# AccessControlBoard.net
KiCad netlist of a schematic drawn in EAGLE
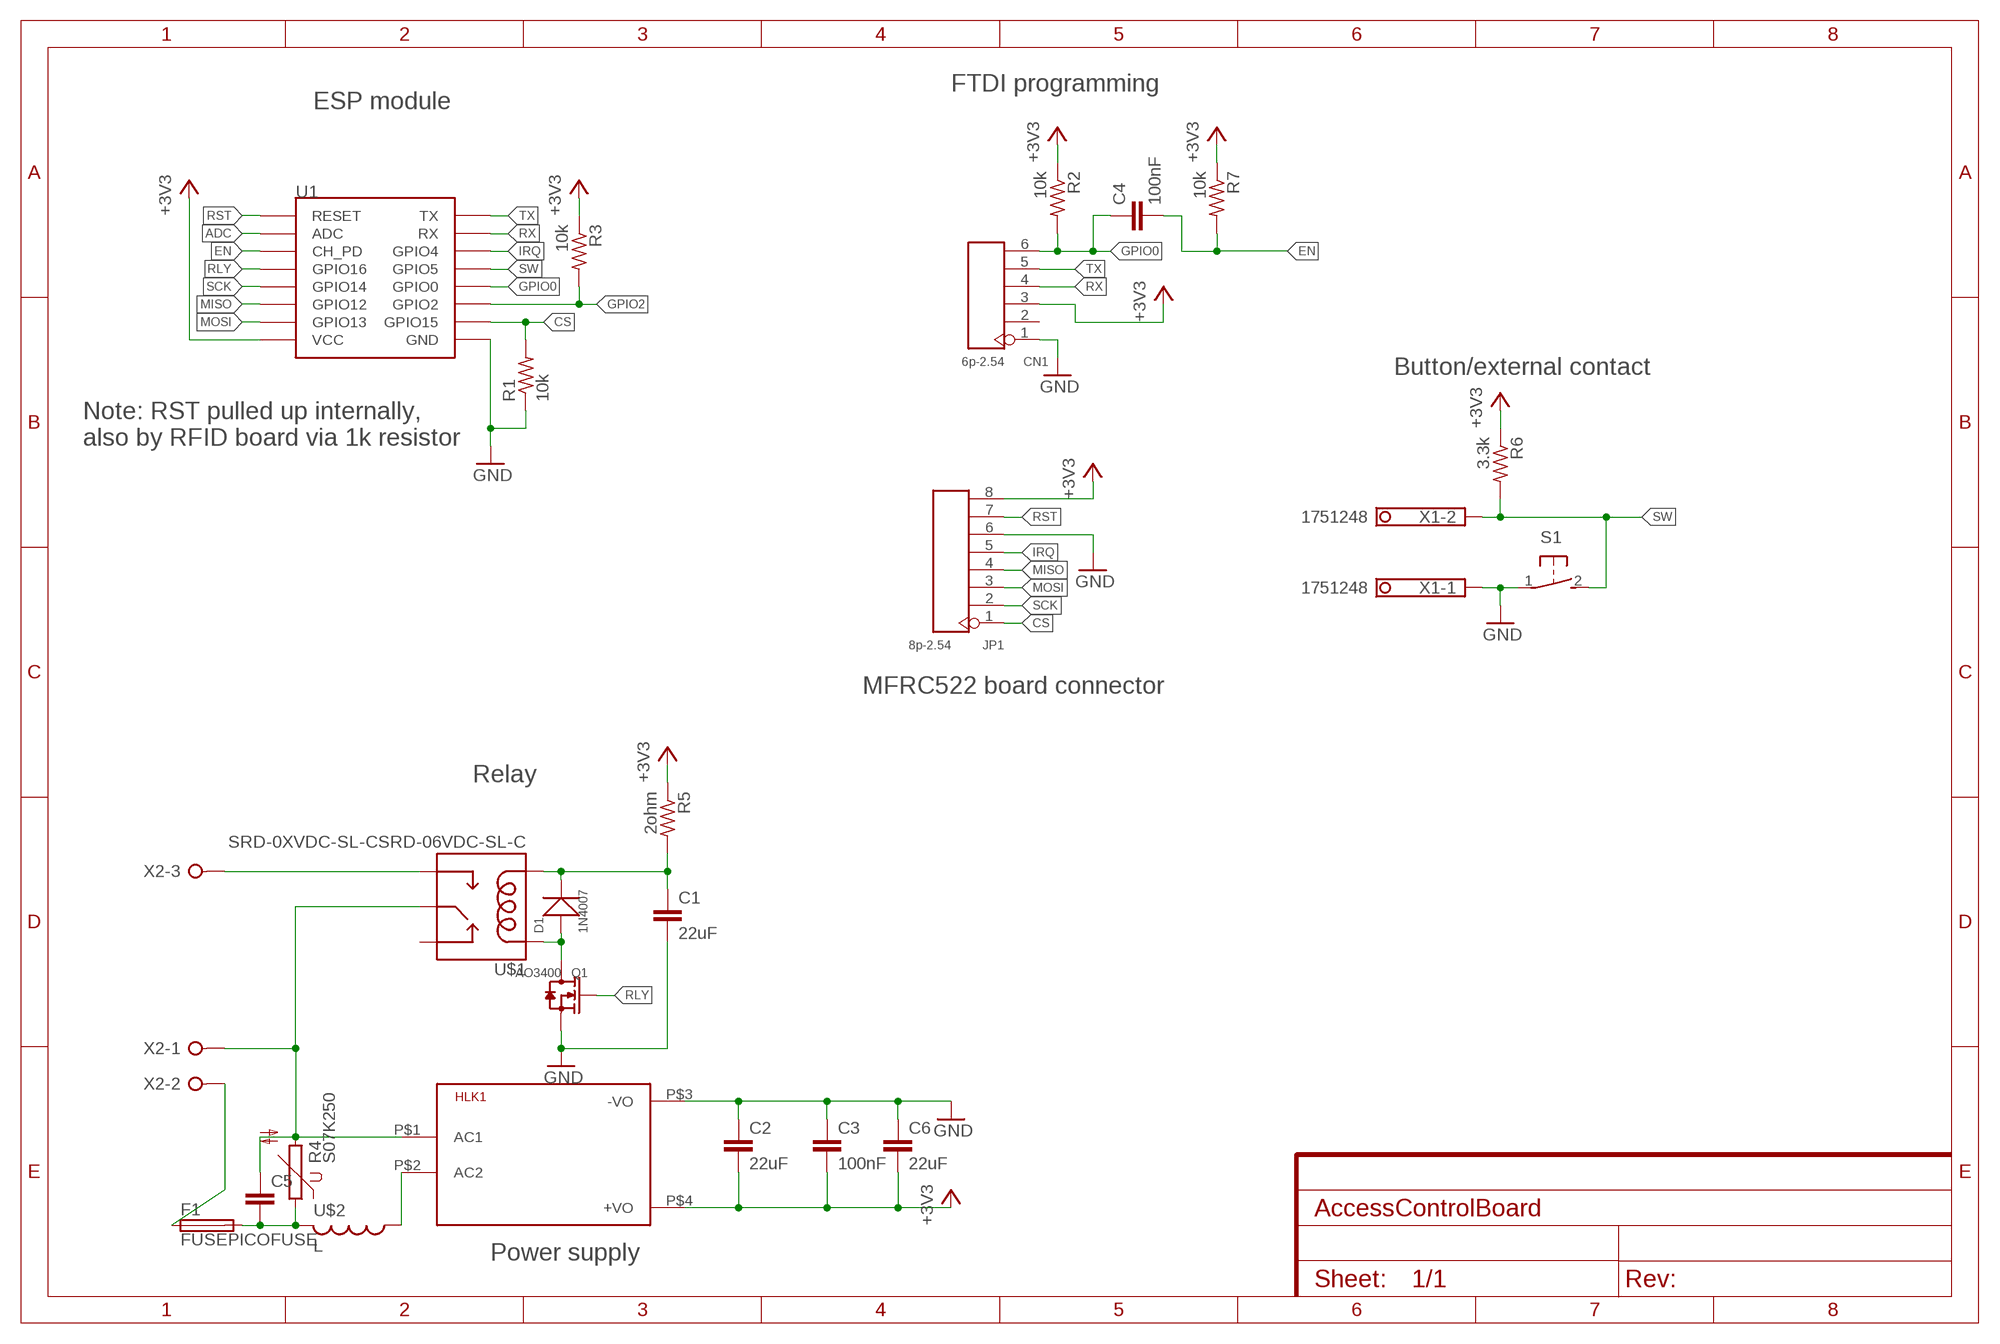
[diagram p0: schematic, sheet 1]

(export (version "E")
  (design (tool "Eeschema 10.0.6"))
  (components
    (comp (ref "C1")
      (value "22uF")
      (footprint "eagle-import:C0805K")
      (libsource (lib "eagle-import") (part "C-EUC0805K"))
    )
    (comp (ref "C2")
      (value "22uF")
      (footprint "eagle-import:C0805K")
      (libsource (lib "eagle-import") (part "C-EUC0805K"))
    )
    (comp (ref "C3")
      (value "100nF")
      (footprint "eagle-import:C0603K")
      (libsource (lib "eagle-import") (part "C-EUC0603K"))
    )
    (comp (ref "C4")
      (value "100nF")
      (footprint "eagle-import:C0603K")
      (libsource (lib "eagle-import") (part "C-EUC0603K"))
    )
    (comp (ref "C5")
      (value "C-EU102-064X133")
      (footprint "eagle-import:C102-064X133")
      (libsource (lib "eagle-import") (part "C-EU102-064X133"))
    )
    (comp (ref "C6")
      (value "22uF")
      (footprint "eagle-import:C0805K")
      (libsource (lib "eagle-import") (part "C-EUC0805K"))
    )
    (comp (ref "CN1")
      (value "6p-2.54")
      (footprint "eagle-import:H6-2.54")
      (fields (field (name "MPN") "F185-1106A1BSYC1"))
      (libsource (lib "eagle-import") (part "DIP-BLACK-FEMALE-HEADER-VERT(6P-2.54)"))
    )
    (comp (ref "D1")
      (value "1N4007")
      (footprint "eagle-import:DO-214AC")
      (libsource (lib "eagle-import") (part "DIODE-GEN-PURPOSE-1KV-1A(DO-214AC)"))
    )
    (comp (ref "F1")
      (value "FUSEPICOFUSE")
      (footprint "eagle-import:PICOFUSE")
      (libsource (lib "eagle-import") (part "FUSEPICOFUSE"))
    )
    (comp (ref "HLK1")
      (value "HLK-PM013W")
      (footprint "eagle-import:HLK-PM01")
      (libsource (lib "eagle-import") (part "HLK-PM013W"))
    )
    (comp (ref "JP1")
      (value "8p-2.54")
      (footprint "eagle-import:H8-2.54")
      (fields (field (name "MPN") "P125-1108A1BS116A1"))
      (libsource (lib "eagle-import") (part "DIP-BLACK-MALE-HEADER-VERT(8P-2.54)"))
    )
    (comp (ref "Q1")
      (value "AO3400")
      (footprint "eagle-import:SOT-23")
      (fields (field (name "MPN") "2N7002,215"))
      (libsource (lib "eagle-import") (part "SMD-MOSFET-N-CH-60V-300MA-LOGIC-LEVEL-FET-2N7002(SOT-23)"))
    )
    (comp (ref "R1")
      (value "10k")
      (footprint "eagle-import:R0603")
      (libsource (lib "eagle-import") (part "R-US_R0603"))
    )
    (comp (ref "R2")
      (value "10k")
      (footprint "eagle-import:R0603")
      (libsource (lib "eagle-import") (part "R-US_R0603"))
    )
    (comp (ref "R3")
      (value "10k")
      (footprint "eagle-import:R0603")
      (libsource (lib "eagle-import") (part "R-US_R0603"))
    )
    (comp (ref "R4")
      (value "S07K250")
      (footprint "eagle-import:S07K250")
      (libsource (lib "eagle-import") (part "S07K250"))
    )
    (comp (ref "R5")
      (value "2ohm")
      (footprint "eagle-import:R0603")
      (libsource (lib "eagle-import") (part "R-US_R0603"))
    )
    (comp (ref "R6")
      (value "3.3k")
      (footprint "eagle-import:R0603")
      (libsource (lib "eagle-import") (part "R-US_R0603"))
    )
    (comp (ref "R7")
      (value "10k")
      (footprint "eagle-import:R0603")
      (libsource (lib "eagle-import") (part "R-US_R0603"))
    )
    (comp (ref "S1")
      (value "31-XX")
      (footprint "eagle-import:B3F-31XX")
      (fields (field (name "MPN") "B3F-3100"))
      (libsource (lib "eagle-import") (part "31-XX"))
    )
    (comp (ref "U$1")
      (value "SRD-0XVDC-SL-CSRD-06VDC-SL-C")
      (footprint "eagle-import:SRD-0XVDC-SL-C")
      (libsource (lib "eagle-import") (part "SRD-0XVDC-SL-CSRD-06VDC-SL-C"))
    )
    (comp (ref "U$2") (value "L") (footprint "eagle-import:6000") (libsource (lib "eagle-import") (part "L")))
    (comp (ref "U1")
      (value "ESP12SMD")
      (footprint "eagle-import:ESP12-SMD")
      (libsource (lib "eagle-import") (part "ESP12SMD"))
    )
    (comp (ref "X1")
      (value "1751248")
      (footprint "eagle-import:1751248")
      (libsource (lib "eagle-import") (part "1751248"))
    )
    (comp (ref "X2")
      (value "W237-3E")
      (footprint "eagle-import:W237-3E")
      (libsource (lib "eagle-import") (part "W237-3E"))
    )
  )
  (nets
    (net (code "1") (name "+3V3") (class "Default")
      (node (ref "C2") (pin "2") (pinfunction "2_2") (pintype "passive"))
      (node (ref "C3") (pin "2") (pinfunction "2_2") (pintype "passive"))
      (node (ref "C6") (pin "2") (pinfunction "2_2") (pintype "passive"))
      (node (ref "CN1") (pin "3") (pinfunction "3_3") (pintype "bidirectional"))
      (node (ref "HLK1") (pin "P$4") (pinfunction "+VO_P$4") (pintype "bidirectional"))
      (node (ref "JP1") (pin "8") (pinfunction "8_8") (pintype "bidirectional"))
      (node (ref "R2") (pin "1") (pinfunction "1_1") (pintype "passive"))
      (node (ref "R3") (pin "1") (pinfunction "1_1") (pintype "passive"))
      (node (ref "R5") (pin "1") (pinfunction "1_1") (pintype "passive"))
      (node (ref "R6") (pin "1") (pinfunction "1_1") (pintype "passive"))
      (node (ref "R7") (pin "1") (pinfunction "1_1") (pintype "passive"))
      (node (ref "U1") (pin "VCC") (pinfunction "VCC_VCC") (pintype "bidirectional"))
    )
    (net (code "2") (name "ADC") (class "Default")
      (node (ref "U1") (pin "ADC") (pinfunction "ADC_ADC") (pintype "bidirectional"))
    )
    (net (code "3") (name "CS") (class "Default")
      (node (ref "JP1") (pin "1") (pinfunction "1_1") (pintype "bidirectional"))
      (node (ref "R1") (pin "2") (pinfunction "2_2") (pintype "passive"))
      (node (ref "U1") (pin "GPIO15") (pinfunction "GPIO15_GPIO15") (pintype "bidirectional"))
    )
    (net (code "4") (name "EN") (class "Default")
      (node (ref "C4") (pin "2") (pinfunction "2_2") (pintype "passive"))
      (node (ref "R7") (pin "2") (pinfunction "2_2") (pintype "passive"))
      (node (ref "U1") (pin "CH_PD") (pinfunction "CH_PD_CH_PD") (pintype "bidirectional"))
    )
    (net (code "5") (name "GND") (class "Default")
      (node (ref "C1") (pin "2") (pinfunction "2_2") (pintype "passive"))
      (node (ref "C2") (pin "1") (pinfunction "1_1") (pintype "passive"))
      (node (ref "C3") (pin "1") (pinfunction "1_1") (pintype "passive"))
      (node (ref "C6") (pin "1") (pinfunction "1_1") (pintype "passive"))
      (node (ref "CN1") (pin "1") (pinfunction "1_1") (pintype "bidirectional"))
      (node (ref "HLK1") (pin "P$3") (pinfunction "-VO_P$3") (pintype "bidirectional"))
      (node (ref "JP1") (pin "6") (pinfunction "6_6") (pintype "bidirectional"))
      (node (ref "Q1") (pin "2") (pinfunction "S_2") (pintype "passive"))
      (node (ref "R1") (pin "1") (pinfunction "1_1") (pintype "passive"))
      (node (ref "S1") (pin "1") (pinfunction "P_1") (pintype "passive"))
      (node (ref "U1") (pin "GND") (pinfunction "GND_GND") (pintype "bidirectional"))
      (node (ref "X1") (pin "1") (pinfunction "K_1") (pintype "passive"))
    )
    (net (code "6") (name "GPIO0") (class "Default")
      (node (ref "C4") (pin "1") (pinfunction "1_1") (pintype "passive"))
      (node (ref "CN1") (pin "6") (pinfunction "6_6") (pintype "bidirectional"))
      (node (ref "R2") (pin "2") (pinfunction "2_2") (pintype "passive"))
      (node (ref "U1") (pin "GPIO0") (pinfunction "GPIO0_GPIO0") (pintype "bidirectional"))
    )
    (net (code "7") (name "GPIO2") (class "Default")
      (node (ref "R3") (pin "2") (pinfunction "2_2") (pintype "passive"))
      (node (ref "U1") (pin "GPIO2") (pinfunction "GPIO2_GPIO2") (pintype "bidirectional"))
    )
    (net (code "8") (name "IRQ") (class "Default")
      (node (ref "JP1") (pin "5") (pinfunction "5_5") (pintype "bidirectional"))
      (node (ref "U1") (pin "GPIO4") (pinfunction "GPIO4_GPIO4") (pintype "bidirectional"))
    )
    (net (code "9") (name "MISO") (class "Default")
      (node (ref "JP1") (pin "4") (pinfunction "4_4") (pintype "bidirectional"))
      (node (ref "U1") (pin "GPIO12") (pinfunction "GPIO12_GPIO12") (pintype "bidirectional"))
    )
    (net (code "10") (name "MOSI") (class "Default")
      (node (ref "JP1") (pin "3") (pinfunction "3_3") (pintype "bidirectional"))
      (node (ref "U1") (pin "GPIO13") (pinfunction "GPIO13_GPIO13") (pintype "bidirectional"))
    )
    (net (code "11") (name "Net-(C5-Pad2)") (class "Default")
      (node (ref "C5") (pin "2") (pinfunction "2_2") (pintype "passive"))
      (node (ref "F1") (pin "2") (pinfunction "2_2") (pintype "passive"))
      (node (ref "R4") (pin "1") (pinfunction "1_1") (pintype "passive"))
      (node (ref "U$2") (pin "2") (pinfunction "2_2") (pintype "passive"))
    )
    (net (code "12") (name "Net-(D1-+)") (class "Default")
      (node (ref "D1") (pin "1") (pinfunction "+_1") (pintype "passive"))
      (node (ref "Q1") (pin "3") (pinfunction "D_3") (pintype "passive"))
      (node (ref "U$1") (pin "COIL1") (pinfunction "COIL1_COIL1") (pintype "bidirectional"))
    )
    (net (code "13") (name "Net-(D1--)") (class "Default")
      (node (ref "C1") (pin "1") (pinfunction "1_1") (pintype "passive"))
      (node (ref "D1") (pin "2") (pinfunction "-_2") (pintype "passive"))
      (node (ref "R5") (pin "2") (pinfunction "2_2") (pintype "passive"))
      (node (ref "U$1") (pin "COIL0") (pinfunction "COIL0_COIL0") (pintype "bidirectional"))
    )
    (net (code "14") (name "Net-(HLK1-AC1)") (class "Default")
      (node (ref "C5") (pin "1") (pinfunction "1_1") (pintype "passive"))
      (node (ref "HLK1") (pin "P$1") (pinfunction "AC1_P$1") (pintype "bidirectional"))
      (node (ref "R4") (pin "2") (pinfunction "2_2") (pintype "passive"))
      (node (ref "U$1") (pin "SWCOMMON") (pinfunction "SWCOMMON_SWCOMMON") (pintype "bidirectional"))
      (node (ref "X2") (pin "1") (pinfunction "KL_1") (pintype "passive"))
    )
    (net (code "15") (name "Net-(HLK1-AC2)") (class "Default")
      (node (ref "HLK1") (pin "P$2") (pinfunction "AC2_P$2") (pintype "bidirectional"))
      (node (ref "U$2") (pin "1") (pinfunction "1_1") (pintype "passive"))
    )
    (net (code "16") (name "Net-(X2B-KL)") (class "Default")
      (node (ref "F1") (pin "1") (pinfunction "1_1") (pintype "passive"))
      (node (ref "X2") (pin "2") (pinfunction "KL_2") (pintype "passive"))
    )
    (net (code "17") (name "Net-(X2C-KL)") (class "Default")
      (node (ref "U$1") (pin "SWOPEN") (pinfunction "SWOPEN_SWOPEN") (pintype "bidirectional"))
      (node (ref "X2") (pin "3") (pinfunction "KL_3") (pintype "passive"))
    )
    (net (code "18") (name "RLY") (class "Default")
      (node (ref "Q1") (pin "1") (pinfunction "G_1") (pintype "passive"))
      (node (ref "U1") (pin "GPIO16") (pinfunction "GPIO16_GPIO16") (pintype "bidirectional"))
    )
    (net (code "19") (name "RST") (class "Default")
      (node (ref "JP1") (pin "7") (pinfunction "7_7") (pintype "bidirectional"))
      (node (ref "U1") (pin "RESET") (pinfunction "RESET_RESET") (pintype "bidirectional"))
    )
    (net (code "20") (name "RX") (class "Default")
      (node (ref "CN1") (pin "4") (pinfunction "4_4") (pintype "bidirectional"))
      (node (ref "U1") (pin "RXD0") (pinfunction "RX_RXD0") (pintype "bidirectional"))
    )
    (net (code "21") (name "SCK") (class "Default")
      (node (ref "JP1") (pin "2") (pinfunction "2_2") (pintype "bidirectional"))
      (node (ref "U1") (pin "GPIO14") (pinfunction "GPIO14_GPIO14") (pintype "bidirectional"))
    )
    (net (code "22") (name "SW") (class "Default")
      (node (ref "R6") (pin "2") (pinfunction "2_2") (pintype "passive"))
      (node (ref "S1") (pin "2") (pinfunction "S_2") (pintype "passive"))
      (node (ref "U1") (pin "GPIO5") (pinfunction "GPIO5_GPIO5") (pintype "bidirectional"))
      (node (ref "X1") (pin "2") (pinfunction "K_2") (pintype "passive"))
    )
    (net (code "23") (name "TX") (class "Default")
      (node (ref "CN1") (pin "5") (pinfunction "5_5") (pintype "bidirectional"))
      (node (ref "U1") (pin "TXD0") (pinfunction "TX_TXD0") (pintype "bidirectional"))
    )
    (net (code "24") (name "unconnected-(CN1-Pad2)") (class "Default")
      (node (ref "CN1") (pin "2") (pinfunction "2_2") (pintype "bidirectional"))
    )
    (net (code "25") (name "unconnected-(U$1-SWCLOSE-PadSWCLOSED)") (class "Default")
      (node (ref "U$1") (pin "SWCLOSED") (pinfunction "SWCLOSE_SWCLOSED") (pintype "bidirectional"))
    )
  )
)
